# Energy_Meter_Final.net
KiCad netlist of a schematic drawn in EasyEDA
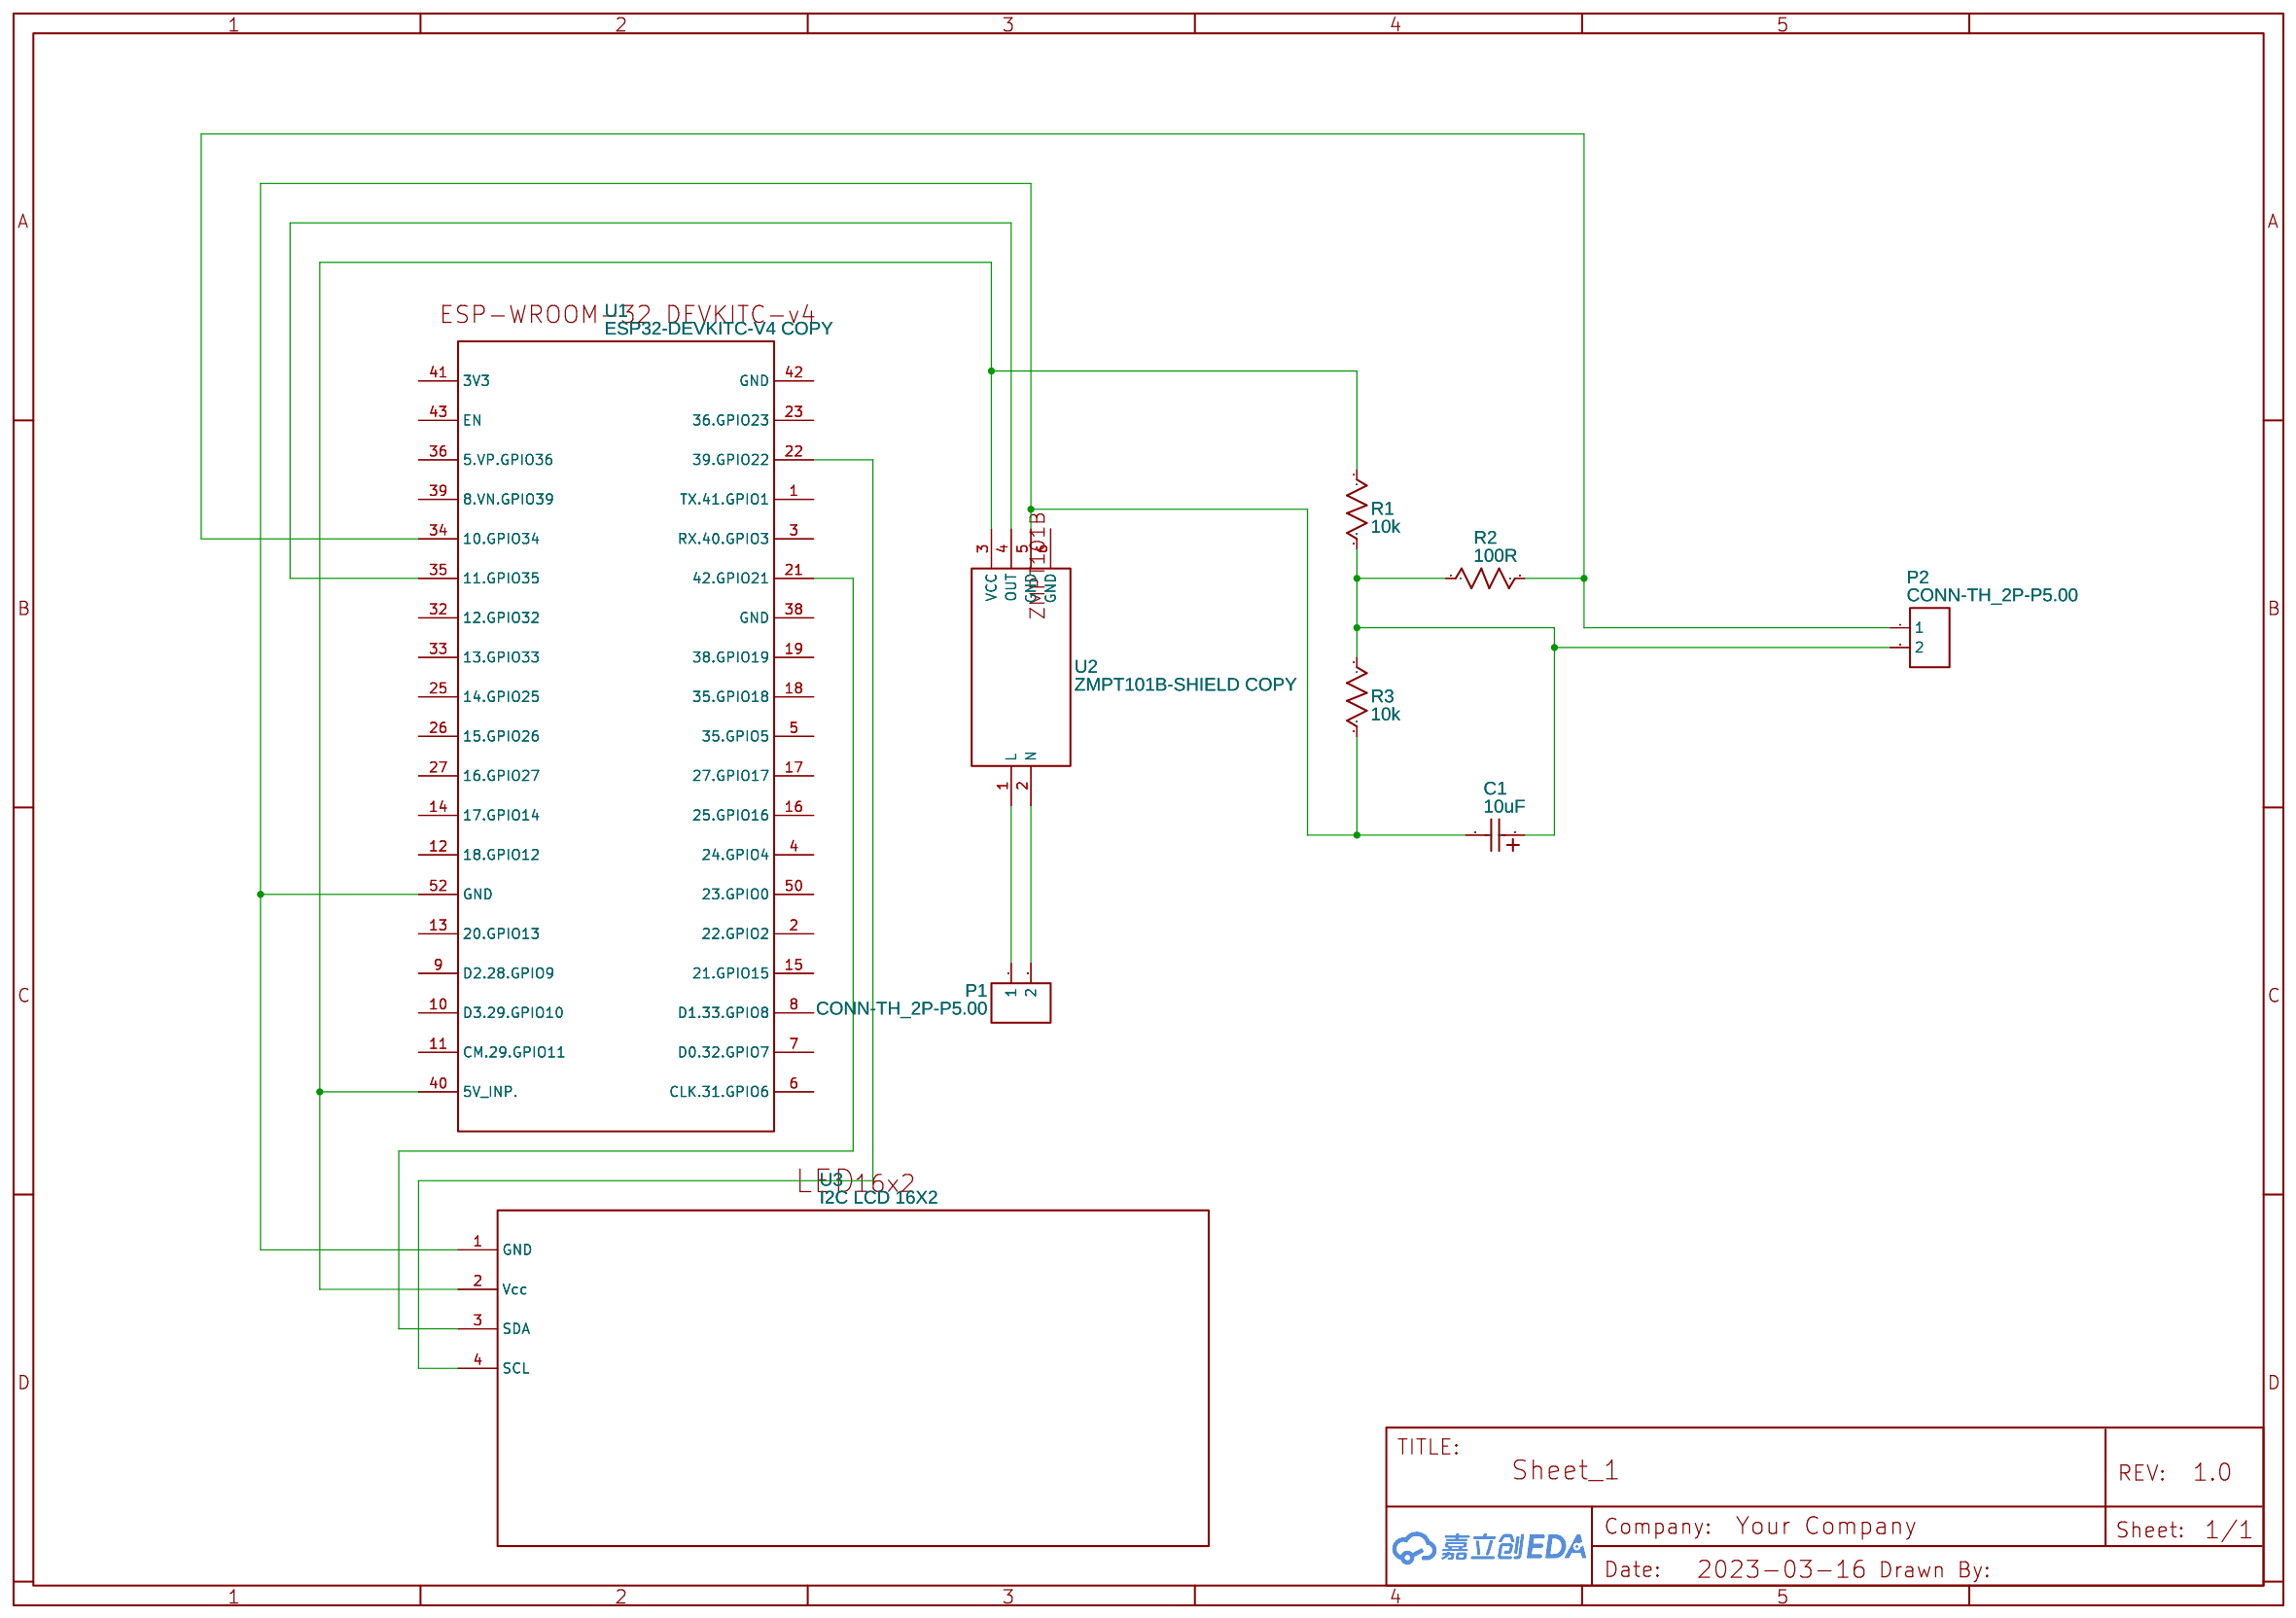
[diagram p0: schematic sheet]

(export (version "E")
  (design (tool "Eeschema 10.0.6"))
  (components
    (comp (ref "C1")
      (value "10uF")
      (fields
        (field (name "BOM_Manufacturer Part") "ESK106M025AC3AA")
        (field (name "BOM_Supplier Part") "2068976")
      )
      (libsource (lib "") (part "10uF"))
    )
    (comp (ref "P1") (value "CONN-TH_2P-P5.00") (libsource (lib "") (part "CONN-TH_2P-P5.00_1")))
    (comp (ref "P2") (value "CONN-TH_2P-P5.00") (libsource (lib "") (part "CONN-TH_2P-P5.00")))
    (comp (ref "R1") (value "10k") (libsource (lib "") (part "R_AXIAL-0.5_US")))
    (comp (ref "R2") (value "100R") (libsource (lib "") (part "R_AXIAL-0.5_US_1")))
    (comp (ref "R3") (value "10k") (libsource (lib "") (part "R_AXIAL-0.5_US")))
    (comp (ref "U1")
      (value "ESP32-DEVKITC-V4 COPY")
      (fields
        (field (name "BOM_Manufacturer Part") "ESP32-DevKitC")
        (field (name "BOM_Supplier Part") "356-ESP32-DEVKITC")
      )
      (libsource (lib "") (part "ESP32-DEVKITC-V4 COPY"))
    )
    (comp (ref "U2") (value "ZMPT101B-SHIELD COPY") (libsource (lib "") (part "ZMPT101B-SHIELD COPY")))
    (comp (ref "U3") (value "I2C LCD 16X2") (libsource (lib "") (part "I2C LCD 16X2")))
  )
  (nets
    (net (code "1") (name "Net-(C1-Pad1)") (class "Default")
      (node (ref "C1") (pin "1") (pinfunction "1_1") (pintype "input"))
      (node (ref "P2") (pin "2") (pinfunction "2_2") (pintype "unspecified"))
      (node (ref "R1") (pin "2") (pinfunction "2_2") (pintype "unspecified"))
      (node (ref "R2") (pin "1") (pinfunction "1_1") (pintype "unspecified"))
      (node (ref "R3") (pin "1") (pinfunction "1_1") (pintype "unspecified"))
    )
    (net (code "2") (name "Net-(U1-5V_INP.)") (class "Default")
      (node (ref "R1") (pin "1") (pinfunction "1_1") (pintype "unspecified"))
      (node (ref "U1") (pin "40") (pinfunction "5V_INP._40") (pintype "unspecified"))
      (node (ref "U2") (pin "3") (pinfunction "VCC_3") (pintype "unspecified"))
      (node (ref "U3") (pin "2") (pinfunction "Vcc_2") (pintype "unspecified"))
    )
    (net (code "3") (name "Net-(U1-10.GPIO34)") (class "Default")
      (node (ref "P2") (pin "1") (pinfunction "1_1") (pintype "unspecified"))
      (node (ref "R2") (pin "2") (pinfunction "2_2") (pintype "unspecified"))
      (node (ref "U1") (pin "34") (pinfunction "10.GPIO34_34") (pintype "unspecified"))
    )
    (net (code "4") (name "Net-(U1-11.GPIO35)") (class "Default")
      (node (ref "U1") (pin "35") (pinfunction "11.GPIO35_35") (pintype "unspecified"))
      (node (ref "U2") (pin "4") (pinfunction "OUT_4") (pintype "unspecified"))
    )
    (net (code "5") (name "Net-(U1-39.GPIO22)") (class "Default")
      (node (ref "U1") (pin "22") (pinfunction "39.GPIO22_22") (pintype "unspecified"))
      (node (ref "U3") (pin "4") (pinfunction "SCL_4") (pintype "unspecified"))
    )
    (net (code "6") (name "Net-(U1-42.GPIO21)") (class "Default")
      (node (ref "U1") (pin "21") (pinfunction "42.GPIO21_21") (pintype "unspecified"))
      (node (ref "U3") (pin "3") (pinfunction "SDA_3") (pintype "unspecified"))
    )
    (net (code "7") (name "Net-(U2-L)") (class "Default")
      (node (ref "P1") (pin "1") (pinfunction "1_1") (pintype "unspecified"))
      (node (ref "U2") (pin "1") (pinfunction "L_1") (pintype "unspecified"))
    )
    (net (code "8") (name "Net-(U2-N)") (class "Default")
      (node (ref "P1") (pin "2") (pinfunction "2_2") (pintype "unspecified"))
      (node (ref "U2") (pin "2") (pinfunction "N_2") (pintype "unspecified"))
    )
    (net (code "9") (name "Net-(U3-GND)") (class "Default")
      (node (ref "C1") (pin "2") (pinfunction "2_2") (pintype "input"))
      (node (ref "R3") (pin "2") (pinfunction "2_2") (pintype "unspecified"))
      (node (ref "U1") (pin "52") (pinfunction "GND_52") (pintype "unspecified"))
      (node (ref "U2") (pin "5") (pinfunction "GND_5") (pintype "unspecified"))
      (node (ref "U3") (pin "1") (pinfunction "GND_1") (pintype "unspecified"))
    )
    (net (code "10") (name "unconnected-(U1-3V3-Pad41)") (class "Default")
      (node (ref "U1") (pin "41") (pinfunction "3V3_41") (pintype "unspecified"))
    )
    (net (code "11") (name "unconnected-(U1-5.VP.GPIO36-Pad36)") (class "Default")
      (node (ref "U1") (pin "36") (pinfunction "5.VP.GPIO36_36") (pintype "unspecified"))
    )
    (net (code "12") (name "unconnected-(U1-8.VN.GPIO39-Pad39)") (class "Default")
      (node (ref "U1") (pin "39") (pinfunction "8.VN.GPIO39_39") (pintype "unspecified"))
    )
    (net (code "13") (name "unconnected-(U1-12.GPIO32-Pad32)") (class "Default")
      (node (ref "U1") (pin "32") (pinfunction "12.GPIO32_32") (pintype "unspecified"))
    )
    (net (code "14") (name "unconnected-(U1-13.GPIO33-Pad33)") (class "Default")
      (node (ref "U1") (pin "33") (pinfunction "13.GPIO33_33") (pintype "unspecified"))
    )
    (net (code "15") (name "unconnected-(U1-14.GPIO25-Pad25)") (class "Default")
      (node (ref "U1") (pin "25") (pinfunction "14.GPIO25_25") (pintype "unspecified"))
    )
    (net (code "16") (name "unconnected-(U1-15.GPIO26-Pad26)") (class "Default")
      (node (ref "U1") (pin "26") (pinfunction "15.GPIO26_26") (pintype "unspecified"))
    )
    (net (code "17") (name "unconnected-(U1-16.GPIO27-Pad27)") (class "Default")
      (node (ref "U1") (pin "27") (pinfunction "16.GPIO27_27") (pintype "unspecified"))
    )
    (net (code "18") (name "unconnected-(U1-17.GPIO14-Pad14)") (class "Default")
      (node (ref "U1") (pin "14") (pinfunction "17.GPIO14_14") (pintype "unspecified"))
    )
    (net (code "19") (name "unconnected-(U1-18.GPIO12-Pad12)") (class "Default")
      (node (ref "U1") (pin "12") (pinfunction "18.GPIO12_12") (pintype "unspecified"))
    )
    (net (code "20") (name "unconnected-(U1-20.GPIO13-Pad13)") (class "Default")
      (node (ref "U1") (pin "13") (pinfunction "20.GPIO13_13") (pintype "unspecified"))
    )
    (net (code "21") (name "unconnected-(U1-21.GPIO15-Pad15)") (class "Default")
      (node (ref "U1") (pin "15") (pinfunction "21.GPIO15_15") (pintype "unspecified"))
    )
    (net (code "22") (name "unconnected-(U1-22.GPIO2-Pad2)") (class "Default")
      (node (ref "U1") (pin "2") (pinfunction "22.GPIO2_2") (pintype "unspecified"))
    )
    (net (code "23") (name "unconnected-(U1-23.GPIO0-Pad50)") (class "Default")
      (node (ref "U1") (pin "50") (pinfunction "23.GPIO0_50") (pintype "unspecified"))
    )
    (net (code "24") (name "unconnected-(U1-24.GPIO4-Pad4)") (class "Default")
      (node (ref "U1") (pin "4") (pinfunction "24.GPIO4_4") (pintype "unspecified"))
    )
    (net (code "25") (name "unconnected-(U1-25.GPIO16-Pad16)") (class "Default")
      (node (ref "U1") (pin "16") (pinfunction "25.GPIO16_16") (pintype "unspecified"))
    )
    (net (code "26") (name "unconnected-(U1-27.GPIO17-Pad17)") (class "Default")
      (node (ref "U1") (pin "17") (pinfunction "27.GPIO17_17") (pintype "unspecified"))
    )
    (net (code "27") (name "unconnected-(U1-35.GPIO5-Pad5)") (class "Default")
      (node (ref "U1") (pin "5") (pinfunction "35.GPIO5_5") (pintype "unspecified"))
    )
    (net (code "28") (name "unconnected-(U1-35.GPIO18-Pad18)") (class "Default")
      (node (ref "U1") (pin "18") (pinfunction "35.GPIO18_18") (pintype "unspecified"))
    )
    (net (code "29") (name "unconnected-(U1-36.GPIO23-Pad23)") (class "Default")
      (node (ref "U1") (pin "23") (pinfunction "36.GPIO23_23") (pintype "unspecified"))
    )
    (net (code "30") (name "unconnected-(U1-38.GPIO19-Pad19)") (class "Default")
      (node (ref "U1") (pin "19") (pinfunction "38.GPIO19_19") (pintype "unspecified"))
    )
    (net (code "31") (name "unconnected-(U1-CLK.31.GPIO6-Pad6)") (class "Default")
      (node (ref "U1") (pin "6") (pinfunction "CLK.31.GPIO6_6") (pintype "unspecified"))
    )
    (net (code "32") (name "unconnected-(U1-CM.29.GPIO11-Pad11)") (class "Default")
      (node (ref "U1") (pin "11") (pinfunction "CM.29.GPIO11_11") (pintype "unspecified"))
    )
    (net (code "33") (name "unconnected-(U1-D0.32.GPIO7-Pad7)") (class "Default")
      (node (ref "U1") (pin "7") (pinfunction "D0.32.GPIO7_7") (pintype "unspecified"))
    )
    (net (code "34") (name "unconnected-(U1-D1.33.GPIO8-Pad8)") (class "Default")
      (node (ref "U1") (pin "8") (pinfunction "D1.33.GPIO8_8") (pintype "unspecified"))
    )
    (net (code "35") (name "unconnected-(U1-D2.28.GPIO9-Pad9)") (class "Default")
      (node (ref "U1") (pin "9") (pinfunction "D2.28.GPIO9_9") (pintype "unspecified"))
    )
    (net (code "36") (name "unconnected-(U1-D3.29.GPIO10-Pad10)") (class "Default")
      (node (ref "U1") (pin "10") (pinfunction "D3.29.GPIO10_10") (pintype "unspecified"))
    )
    (net (code "37") (name "unconnected-(U1-EN-Pad43)") (class "Default")
      (node (ref "U1") (pin "43") (pinfunction "EN_43") (pintype "unspecified"))
    )
    (net (code "38") (name "unconnected-(U1-GND-Pad38)") (class "Default")
      (node (ref "U1") (pin "38") (pinfunction "GND_38") (pintype "unspecified"))
    )
    (net (code "39") (name "unconnected-(U1-GND-Pad42)") (class "Default")
      (node (ref "U1") (pin "42") (pinfunction "GND_42") (pintype "unspecified"))
    )
    (net (code "40") (name "unconnected-(U1-RX.40.GPIO3-Pad3)") (class "Default")
      (node (ref "U1") (pin "3") (pinfunction "RX.40.GPIO3_3") (pintype "unspecified"))
    )
    (net (code "41") (name "unconnected-(U1-TX.41.GPIO1-Pad1)") (class "Default")
      (node (ref "U1") (pin "1") (pinfunction "TX.41.GPIO1_1") (pintype "unspecified"))
    )
    (net (code "42") (name "unconnected-(U2-GND-Pad6)") (class "Default")
      (node (ref "U2") (pin "6") (pinfunction "GND_6") (pintype "unspecified"))
    )
  )
)
